# MP8756GD_4.net
KiCad netlist of a schematic drawn in Altium Designer
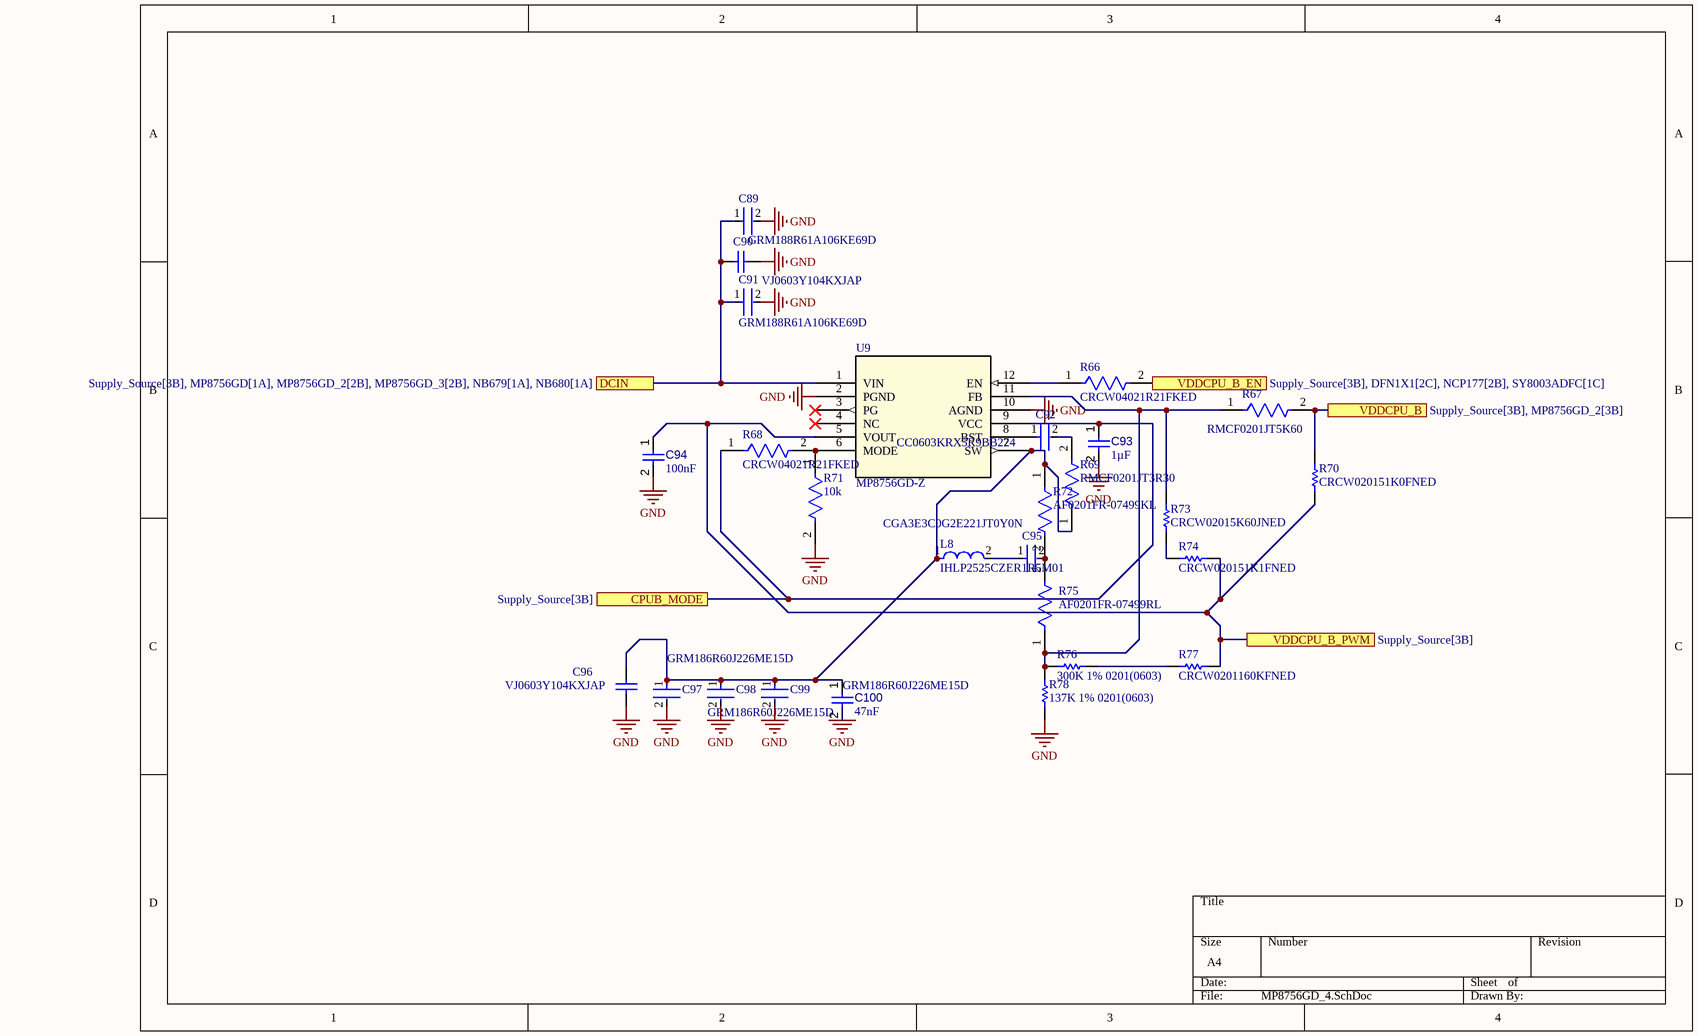
[diagram p0: MP8756GD_4.SchDoc]

(export (version "E")
  (design (tool "Eeschema 10.0.6"))
  (components
    (comp (ref "C89")
      (value "GRM188R61A106KE69D")
      (footprint "FP-GRM18-0_15-MFG")
      (description "CAP CER 10UF 10V X5R 0603")
      (fields
        (field (name "OCTOPART") "https://octopart.com/grm188r61a106ke69d-murata-22851381")
        (field (name "MANUFACTURER") "Murata")
      )
      (libsource (lib "Altium Content Vault") (part "11868f565c42a9108669ba33697ecf6"))
    )
    (comp (ref "C90")
      (value "VJ0603Y104KXJAP")
      (footprint "CAPC1608X92X38NL15T08")
      (fields (field (name "MANUFACTURER") "Vitramon"))
      (libsource (lib "Altium Content Vault") (part "CAP"))
    )
    (comp (ref "C91")
      (value "GRM188R61A106KE69D")
      (footprint "FP-GRM18-0_15-MFG")
      (description "CAP CER 10UF 10V X5R 0603")
      (fields
        (field (name "OCTOPART") "https://octopart.com/grm188r61a106ke69d-murata-22851381")
        (field (name "MANUFACTURER") "Murata")
      )
      (libsource (lib "Altium Content Vault") (part "11868f565c42a9108669ba33697ecf6"))
    )
    (comp (ref "C92")
      (value "CC0603KRX5R9BB224")
      (footprint "FP-CC0603-DA-MFG")
      (description "CC0603 220 nF X5R 10.00% 50 V")
      (fields
        (field (name "TOLERANCE") "0.1")
        (field (name "OCTOPART") "https://octopart.com/cc0603krx5r9bb224-yageo-90326743")
      )
      (libsource (lib "Altium Content Vault") (part "11868f565c42a9108669ba33697ecf6"))
    )
    (comp (ref "C93")
      (value "1µF")
      (footprint "CAPC1005X55X25LL05T10")
      (description "Chip Capacitor, 1 uF, +/- 10%, 6.3 V, 0402 (1005 Metric)")
      (fields (field (name "TOLERANCE") "10%") (field (name "Comment") "Capacitor 1 uF +/- 10% 6.3 V 0402"))
      (libsource (lib "MIGUEL ANGEL ALVAREZ GUZMAN") (part "CAP-NP-2"))
    )
    (comp (ref "C94")
      (value "100nF")
      (footprint "CAPC1005X56X25LL10T15")
      (description "Chip Capacitor, 0.1 uF, +/- 5%, 16 V, 0402 (1005 Metric)")
      (fields (field (name "TOLERANCE") "5%") (field (name "Comment") "Capacitor 0.1 uF +/- 5% 16 V 0402"))
      (libsource (lib "MIGUEL ANGEL ALVAREZ GUZMAN") (part "CAP-NP-2"))
    )
    (comp (ref "C95")
      (value "CGA3E3C0G2E221JT0Y0N")
      (footprint "FP-CGA3E-0_3-0_1-IPC_B")
      (description "Cap Ceramic 220pF 250V C0G 5% Pad SMD 0603 +125°C Automotive T/R")
      (libsource (lib "Altium Content Vault") (part "b4654b650e69147ec39a6b967a45e02"))
    )
    (comp (ref "C96")
      (value "VJ0603Y104KXJAP")
      (footprint "CAPC1608X92X38NL15T08")
      (fields (field (name "MANUFACTURER") "Vitramon"))
      (libsource (lib "Altium Content Vault") (part "CAP"))
    )
    (comp (ref "C97")
      (value "GRM186R60J226ME15D")
      (footprint "FP-GRM186-0_2-IPC_B")
      (description "Chip Multilayer Ceramic Capacitors for General Purpose, 0603, 22uF, X5R, 15%, 20%, 6.3V")
      (fields (field (name "TOLERANCE") "20%"))
      (libsource (lib "Altium Content Vault") (part "02cd4be3c70576c341d710602a673aa"))
    )
    (comp (ref "C98")
      (value "GRM186R60J226ME15D")
      (footprint "FP-GRM186-0_2-IPC_B")
      (description "Chip Multilayer Ceramic Capacitors for General Purpose, 0603, 22uF, X5R, 15%, 20%, 6.3V")
      (fields (field (name "TOLERANCE") "20%"))
      (libsource (lib "Altium Content Vault") (part "02cd4be3c70576c341d710602a673aa"))
    )
    (comp (ref "C99")
      (value "GRM186R60J226ME15D")
      (footprint "FP-GRM186-0_2-IPC_B")
      (description "Chip Multilayer Ceramic Capacitors for General Purpose, 0603, 22uF, X5R, 15%, 20%, 6.3V")
      (fields (field (name "TOLERANCE") "20%"))
      (libsource (lib "Altium Content Vault") (part "02cd4be3c70576c341d710602a673aa"))
    )
    (comp (ref "C100")
      (value "47nF")
      (footprint "CAPC0402(1005)60_L")
      (description "Chip Capacitor, 47nF +/-20%, 50V, 0402, Thickness 0.6 mm")
      (fields (field (name "TOLERANCE") "20%") (field (name "Comment") "Capacitor 47nF +/-20% 50V 0402"))
      (libsource (lib "MIGUEL ANGEL ALVAREZ GUZMAN") (part "CAP-NP-2"))
    )
    (comp (ref "L8")
      (value "IHLP2525CZER1R5M01")
      (footprint "FP-IHLP-2525CZ-FP_2_413x3-MFG")
      (description "Commercial Inductors, High Saturation Series 1.5uH 9A 15mΩ 20%")
      (fields (field (name "TOLERANCE") "20%"))
      (libsource (lib "Altium Content Vault") (part "725321dda6339637d4d059423bc1c3c"))
    )
    (comp (ref "R66")
      (value "CRCW04021R21FKED")
      (footprint "FP-CRCW0402-e3-MFG")
      (description "RES Thick Film, 1.21Ω, 1%, 0.063W, 100ppm/°C, 0402")
      (fields (field (name "TOLERANCE") "1%"))
      (libsource (lib "Altium Content Vault") (part "1029c3af85768c4190bb7ad29bc67b5"))
    )
    (comp (ref "R67")
      (value "RMCF0201JT5K60")
      (footprint "FP-RMCF0201-MFG")
      (description "5.6kΩ ±5% 0.05W 0201 Thick Film Chip Resistor AEC-Q200 compliant")
      (fields (field (name "TOLERANCE") "5%"))
      (libsource (lib "Altium Content Vault") (part "1029c3af85768c4190bb7ad29bc67b5"))
    )
    (comp (ref "R68")
      (value "CRCW04021R21FKED")
      (footprint "FP-CRCW0402-e3-MFG")
      (description "RES Thick Film, 1.21Ω, 1%, 0.063W, 100ppm/°C, 0402")
      (fields (field (name "TOLERANCE") "1%"))
      (libsource (lib "Altium Content Vault") (part "1029c3af85768c4190bb7ad29bc67b5"))
    )
    (comp (ref "R69")
      (value "RMCF0201JT3R30")
      (footprint "FP-RMCF0201-IPC_A")
      (description "3.3Ω ±5% 0.05W 0201 Thick Film Chip Resistor AEC-Q200 compliant")
      (fields (field (name "TOLERANCE") "5%"))
      (libsource (lib "Altium Content Vault") (part "1029c3af85768c4190bb7ad29bc67b5"))
    )
    (comp (ref "R70")
      (value "CRCW020151K0FNED")
      (footprint "RESC0603X28X15LL05T05")
      (fields (field (name "MANUFACTURER") "Vishay Dale"))
      (libsource (lib "Altium Content Vault") (part "RES"))
    )
    (comp (ref "R71")
      (value "10k")
      (footprint "FP-RT0201-IPC_C")
      (description "Fixed Resistor, Thin Film, 0.05W, 10000ohm, 25V, 0.1% +/-Tol, 50ppm/Cel, Surface Mount, 0201")
      (fields (field (name "TOLERANCE") "0.1%") (field (name "Comment") "RT0201BRE0710KL"))
      (libsource (lib "MIGUEL ANGEL ALVAREZ GUZMAN") (part "1029c3af85768c4190bb7ad29bc67b5"))
    )
    (comp (ref "R72")
      (value "AF0201FR-07499KL")
      (footprint "FP-AF0201-MFG")
      (description "Anti-Sulfurated Chip Resistors Automotive Grade 499kΩ 1% 200ppm/°C 0201")
      (fields (field (name "TOLERANCE") "1%"))
      (libsource (lib "Altium Content Vault") (part "1029c3af85768c4190bb7ad29bc67b5"))
    )
    (comp (ref "R73")
      (value "CRCW02015K60JNED")
      (footprint "RESC0603X28X15NL05T05")
      (fields (field (name "MANUFACTURER") "Vishay Dale"))
      (libsource (lib "Altium Content Vault") (part "RES"))
    )
    (comp (ref "R74")
      (value "CRCW020151K1FNED")
      (footprint "RESC0603X28X15ML05T05")
      (fields (field (name "MANUFACTURER") "Vishay Dale"))
      (libsource (lib "Altium Content Vault") (part "RES"))
    )
    (comp (ref "R75")
      (value "AF0201FR-07499RL")
      (footprint "FP-AF0201-IPC_A")
      (description "Anti-Sulfurated Chip Resistors Automotive Grade 499Ω 1% 200ppm/°C 0201")
      (fields (field (name "TOLERANCE") "1%"))
      (libsource (lib "Altium Content Vault") (part "1029c3af85768c4190bb7ad29bc67b5"))
    )
    (comp (ref "R76")
      (value "300K 1% 0201(0603)")
      (footprint "RESC0201(0603)_L")
      (description "300K 0.05W 1% 0201 (0603 Metric)  SMD")
      (fields (field (name "POWER") "0.05 W") (field (name "TOLERANCE") "1 %"))
      (libsource (lib "Altium Content Vault") (part "RES"))
    )
    (comp (ref "R77")
      (value "CRCW0201160KFNED")
      (footprint "RESC0603X28X15ML05T05")
      (fields (field (name "MANUFACTURER") "Vishay Dale"))
      (libsource (lib "Altium Content Vault") (part "RES"))
    )
    (comp (ref "R78")
      (value "137K 1% 0201(0603)")
      (footprint "RESC0201(0603)_M")
      (description "137K 0.05W 1% 0201 (0603 Metric)  SMD")
      (fields (field (name "POWER") "0.05 W") (field (name "TOLERANCE") "1 %"))
      (libsource (lib "Altium Content Vault") (part "RES"))
    )
    (comp (ref "U9")
      (value "MP8756GD-Z")
      (footprint "QFN-12_MP8756_MNP")
      (description "26V 6A Low IQ High-Current Synchronous Step-Down Converter")
      (fields (field (name "COPYRIGHT") "Copyright (C) 2025 Ultra Librarian. All rights reserved."))
      (libsource (lib "MIGUEL ANGEL ALVAREZ GUZMAN") (part "MP8756GD-Z"))
    )
  )
  (nets
    (net (code "1") (name "/CPUB_MODE") (class "Default")
      (node (ref "C93") (pin "1") (pinfunction "1_1") (pintype "passive"))
      (node (ref "R68") (pin "1") (pinfunction "1_1") (pintype "passive"))
      (node (ref "U9") (pin "9") (pinfunction "VCC_9") (pintype "power_in"))
    )
    (net (code "2") (name "/DCIN") (class "Default")
      (node (ref "C89") (pin "1") (pinfunction "1_1") (pintype "passive"))
      (node (ref "C90") (pin "2") (pinfunction "2_2") (pintype "passive"))
      (node (ref "C91") (pin "1") (pinfunction "1_1") (pintype "passive"))
      (node (ref "U9") (pin "1") (pinfunction "VIN_1") (pintype "power_in"))
    )
    (net (code "3") (name "/VDDCPU_B") (class "Default")
      (node (ref "R67") (pin "2") (pinfunction "2_2") (pintype "passive"))
      (node (ref "R70") (pin "1") (pinfunction "1_1") (pintype "passive"))
    )
    (net (code "4") (name "/VDDCPU_B_EN") (class "Default")
      (node (ref "R66") (pin "2") (pinfunction "2_2") (pintype "passive"))
    )
    (net (code "5") (name "/VDDCPU_B_PWM") (class "Default")
      (node (ref "C94") (pin "1") (pinfunction "1_1") (pintype "passive"))
      (node (ref "R70") (pin "2") (pinfunction "2_2") (pintype "passive"))
      (node (ref "R74") (pin "2") (pinfunction "2_2") (pintype "passive"))
      (node (ref "R77") (pin "2") (pinfunction "2_2") (pintype "passive"))
      (node (ref "U9") (pin "5") (pinfunction "VOUT_5") (pintype "power_in"))
    )
    (net (code "6") (name "GND") (class "Default")
      (node (ref "C100") (pin "2") (pinfunction "2_2") (pintype "passive"))
      (node (ref "C89") (pin "2") (pinfunction "2_2") (pintype "passive"))
      (node (ref "C90") (pin "1") (pinfunction "1_1") (pintype "passive"))
      (node (ref "C91") (pin "2") (pinfunction "2_2") (pintype "passive"))
      (node (ref "C93") (pin "2") (pinfunction "2_2") (pintype "passive"))
      (node (ref "C94") (pin "2") (pinfunction "2_2") (pintype "passive"))
      (node (ref "C96") (pin "1") (pinfunction "1_1") (pintype "passive"))
      (node (ref "C97") (pin "2") (pinfunction "2_2") (pintype "passive"))
      (node (ref "C98") (pin "2") (pinfunction "2_2") (pintype "passive"))
      (node (ref "C99") (pin "2") (pinfunction "2_2") (pintype "passive"))
      (node (ref "R71") (pin "2") (pinfunction "2_2") (pintype "passive"))
      (node (ref "R78") (pin "1") (pinfunction "1_1") (pintype "passive"))
      (node (ref "U9") (pin "10") (pinfunction "AGND_10") (pintype "power_in"))
      (node (ref "U9") (pin "2") (pinfunction "PGND_2") (pintype "power_in"))
    )
    (net (code "7") (name "Net-(C92-Pad2)") (class "Default")
      (node (ref "C92") (pin "2") (pinfunction "2_2") (pintype "passive"))
      (node (ref "R69") (pin "2") (pinfunction "2_2") (pintype "passive"))
    )
    (net (code "8") (name "Net-(C95-Pad1)") (class "Default")
      (node (ref "C95") (pin "1") (pinfunction "1_1") (pintype "passive"))
      (node (ref "L8") (pin "2") (pinfunction "2_2") (pintype "passive"))
    )
    (net (code "9") (name "Net-(C95-Pad2)") (class "Default")
      (node (ref "C95") (pin "2") (pinfunction "2_2") (pintype "passive"))
      (node (ref "R72") (pin "2") (pinfunction "2_2") (pintype "passive"))
      (node (ref "R75") (pin "2") (pinfunction "2_2") (pintype "passive"))
    )
    (net (code "10") (name "Net-(R73-Pad2)") (class "Default")
      (node (ref "R73") (pin "2") (pinfunction "2_2") (pintype "passive"))
      (node (ref "R74") (pin "1") (pinfunction "1_1") (pintype "passive"))
    )
    (net (code "11") (name "Net-(R76-Pad2)") (class "Default")
      (node (ref "R76") (pin "2") (pinfunction "2_2") (pintype "passive"))
      (node (ref "R77") (pin "1") (pinfunction "1_1") (pintype "passive"))
    )
    (net (code "12") (name "Net-(U9-BST)") (class "Default")
      (node (ref "C92") (pin "1") (pinfunction "1_1") (pintype "passive"))
      (node (ref "U9") (pin "8") (pinfunction "BST_8") (pintype "power_in"))
    )
    (net (code "13") (name "Net-(U9-EN)") (class "Default")
      (node (ref "R66") (pin "1") (pinfunction "1_1") (pintype "passive"))
      (node (ref "U9") (pin "12") (pinfunction "EN_12") (pintype "input"))
    )
    (net (code "14") (name "Net-(U9-FB)") (class "Default")
      (node (ref "R67") (pin "1") (pinfunction "1_1") (pintype "passive"))
      (node (ref "R73") (pin "1") (pinfunction "1_1") (pintype "passive"))
      (node (ref "R75") (pin "1") (pinfunction "1_1") (pintype "passive"))
      (node (ref "R76") (pin "1") (pinfunction "1_1") (pintype "passive"))
      (node (ref "R78") (pin "2") (pinfunction "2_2") (pintype "passive"))
      (node (ref "U9") (pin "11") (pinfunction "FB_11") (pintype "passive"))
    )
    (net (code "15") (name "Net-(U9-MODE)") (class "Default")
      (node (ref "R68") (pin "2") (pinfunction "2_2") (pintype "passive"))
      (node (ref "R71") (pin "1") (pinfunction "1_1") (pintype "passive"))
      (node (ref "U9") (pin "6") (pinfunction "MODE_6") (pintype "passive"))
    )
    (net (code "16") (name "Net-(U9-SW)") (class "Default")
      (node (ref "C100") (pin "1") (pinfunction "1_1") (pintype "passive"))
      (node (ref "C96") (pin "2") (pinfunction "2_2") (pintype "passive"))
      (node (ref "C97") (pin "1") (pinfunction "1_1") (pintype "passive"))
      (node (ref "C98") (pin "1") (pinfunction "1_1") (pintype "passive"))
      (node (ref "C99") (pin "1") (pinfunction "1_1") (pintype "passive"))
      (node (ref "L8") (pin "1") (pinfunction "1_1") (pintype "passive"))
      (node (ref "R69") (pin "1") (pinfunction "1_1") (pintype "passive"))
      (node (ref "R72") (pin "1") (pinfunction "1_1") (pintype "passive"))
      (node (ref "U9") (pin "7") (pinfunction "SW_7") (pintype "output"))
    )
    (net (code "17") (name "unconnected-(U9-NC-Pad4)") (class "Default")
      (node (ref "U9") (pin "4") (pinfunction "NC_4") (pintype "passive+no_connect"))
    )
    (net (code "18") (name "unconnected-(U9-PG-Pad3)") (class "Default")
      (node (ref "U9") (pin "3") (pinfunction "PG_3") (pintype "output+no_connect"))
    )
  )
)
